# fin_solder.net
KiCad netlist of a schematic drawn in EAGLE
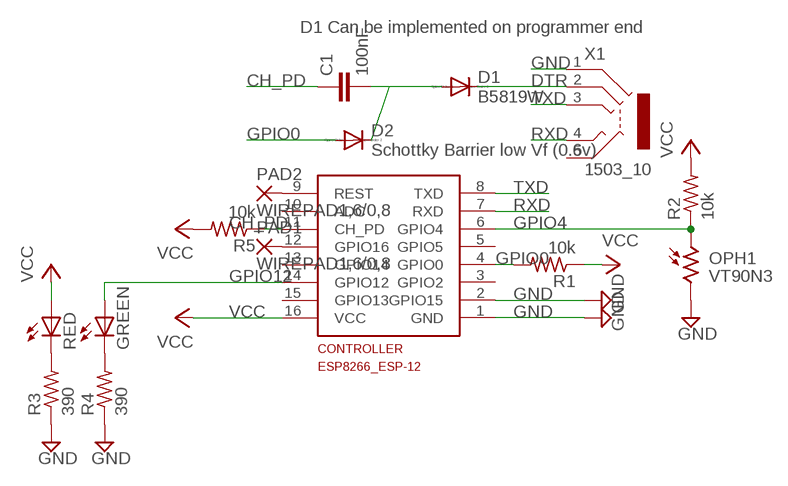
[diagram p0: schematic, sheet 1]

(export (version "E")
  (design (tool "Eeschema 10.0.6"))
  (components
    (comp (ref "C1")
      (value "100nF")
      (footprint "eagle-import:C0603")
      (libsource (lib "eagle-import") (part "C-EUC0603"))
    )
    (comp (ref "CONTROLLER")
      (value "ESP8266_ESP-12")
      (footprint "eagle-import:ESP8266-ESP12")
      (libsource (lib "eagle-import") (part "ESP8266_ESP-12"))
    )
    (comp (ref "D1")
      (value "B5819W")
      (footprint "eagle-import:D-7.5")
      (libsource (lib "eagle-import") (part "DIODE-D-7.5"))
    )
    (comp (ref "D2")
      (value "Schottky Barrier low Vf (0.6v)")
      (footprint "eagle-import:D-7.5")
      (libsource (lib "eagle-import") (part "DIODE-D-7.5"))
    )
    (comp (ref "GREEN")
      (value "LED3MM")
      (footprint "eagle-import:LED3MM")
      (libsource (lib "eagle-import") (part "LED3MM"))
    )
    (comp (ref "OPH1")
      (value "VT90N3")
      (footprint "eagle-import:VT900")
      (libsource (lib "eagle-import") (part "VT90N3"))
    )
    (comp (ref "PAD1")
      (value "WIREPAD1,6/0,8")
      (footprint "eagle-import:1,6_0,8")
      (libsource (lib "eagle-import") (part "WIREPAD1,6/0,8"))
    )
    (comp (ref "PAD2")
      (value "WIREPAD1,6/0,8")
      (footprint "eagle-import:1,6_0,8")
      (libsource (lib "eagle-import") (part "WIREPAD1,6/0,8"))
    )
    (comp (ref "R1")
      (value "10k")
      (footprint "eagle-import:0309_12")
      (libsource (lib "eagle-import") (part "R-US_0309/12"))
    )
    (comp (ref "R2")
      (value "10k")
      (footprint "eagle-import:0309_12")
      (libsource (lib "eagle-import") (part "R-US_0309/12"))
    )
    (comp (ref "R3")
      (value "390")
      (footprint "eagle-import:0309_12")
      (libsource (lib "eagle-import") (part "R-US_0309/12"))
    )
    (comp (ref "R4")
      (value "390")
      (footprint "eagle-import:0309_12")
      (libsource (lib "eagle-import") (part "R-US_0309/12"))
    )
    (comp (ref "R5")
      (value "10k")
      (footprint "eagle-import:0309_12")
      (libsource (lib "eagle-import") (part "R-US_0309/12"))
    )
    (comp (ref "RED")
      (value "LED3MM")
      (footprint "eagle-import:LED3MM")
      (libsource (lib "eagle-import") (part "LED3MM"))
    )
    (comp (ref "X1")
      (value "1503_10")
      (footprint "eagle-import:1503_10")
      (libsource (lib "eagle-import") (part "1503_10"))
    )
  )
  (nets
    (net (code "1") (name "/CH_PD") (class "Default")
      (node (ref "C1") (pin "1") (pinfunction "1_1") (pintype "passive"))
      (node (ref "CONTROLLER") (pin "11") (pinfunction "CH_PD_11") (pintype "bidirectional"))
      (node (ref "R5") (pin "1") (pinfunction "1_1") (pintype "passive"))
    )
    (net (code "2") (name "/DTR") (class "Default")
      (node (ref "D1") (pin "C") (pinfunction "C_C") (pintype "passive"))
      (node (ref "X1") (pin "2") (pinfunction "2_2") (pintype "passive"))
    )
    (net (code "3") (name "/GPIO0") (class "Default")
      (node (ref "CONTROLLER") (pin "4") (pinfunction "GPIO0_4") (pintype "bidirectional"))
      (node (ref "D2") (pin "A") (pinfunction "A_A") (pintype "passive"))
      (node (ref "R1") (pin "2") (pinfunction "2_2") (pintype "passive"))
    )
    (net (code "4") (name "/GPIO4") (class "Default")
      (node (ref "CONTROLLER") (pin "6") (pinfunction "GPIO4_6") (pintype "bidirectional"))
      (node (ref "OPH1") (pin "1") (pinfunction "1_1") (pintype "passive"))
      (node (ref "R2") (pin "1") (pinfunction "1_1") (pintype "passive"))
    )
    (net (code "5") (name "/GPIO12") (class "Default")
      (node (ref "CONTROLLER") (pin "14") (pinfunction "GPIO12_14") (pintype "bidirectional"))
      (node (ref "GREEN") (pin "A") (pinfunction "A_A") (pintype "passive"))
    )
    (net (code "6") (name "/RXD") (class "Default")
      (node (ref "CONTROLLER") (pin "7") (pinfunction "RXD_7") (pintype "bidirectional"))
      (node (ref "X1") (pin "4") (pinfunction "4_4") (pintype "passive"))
    )
    (net (code "7") (name "/TXD") (class "Default")
      (node (ref "CONTROLLER") (pin "8") (pinfunction "TXD_8") (pintype "bidirectional"))
      (node (ref "X1") (pin "3") (pinfunction "3_3") (pintype "passive"))
    )
    (net (code "8") (name "GND") (class "Default")
      (node (ref "CONTROLLER") (pin "1") (pinfunction "GND_1") (pintype "bidirectional"))
      (node (ref "CONTROLLER") (pin "2") (pinfunction "GPIO15_2") (pintype "bidirectional"))
      (node (ref "OPH1") (pin "2") (pinfunction "2_2") (pintype "passive"))
      (node (ref "R3") (pin "1") (pinfunction "1_1") (pintype "passive"))
      (node (ref "R4") (pin "1") (pinfunction "1_1") (pintype "passive"))
      (node (ref "X1") (pin "1") (pinfunction "1_1") (pintype "passive"))
    )
    (net (code "9") (name "Net-(C1-Pad2)") (class "Default")
      (node (ref "C1") (pin "2") (pinfunction "2_2") (pintype "passive"))
      (node (ref "D1") (pin "A") (pinfunction "A_A") (pintype "passive"))
      (node (ref "D2") (pin "C") (pinfunction "C_C") (pintype "passive"))
    )
    (net (code "10") (name "Net-(CONTROLLER-GPIO16)") (class "Default")
      (node (ref "CONTROLLER") (pin "12") (pinfunction "GPIO16_12") (pintype "bidirectional"))
      (node (ref "PAD1") (pin "1") (pinfunction "P_1") (pintype "passive"))
    )
    (net (code "11") (name "Net-(CONTROLLER-REST)") (class "Default")
      (node (ref "CONTROLLER") (pin "9") (pinfunction "REST_9") (pintype "bidirectional"))
      (node (ref "PAD2") (pin "1") (pinfunction "P_1") (pintype "passive"))
    )
    (net (code "12") (name "Net-(GREEN-C)") (class "Default")
      (node (ref "GREEN") (pin "K") (pinfunction "C_K") (pintype "passive"))
      (node (ref "R4") (pin "2") (pinfunction "2_2") (pintype "passive"))
    )
    (net (code "13") (name "Net-(RED-C)") (class "Default")
      (node (ref "R3") (pin "2") (pinfunction "2_2") (pintype "passive"))
      (node (ref "RED") (pin "K") (pinfunction "C_K") (pintype "passive"))
    )
    (net (code "14") (name "VCC") (class "Default")
      (node (ref "CONTROLLER") (pin "16") (pinfunction "VCC_16") (pintype "bidirectional"))
      (node (ref "R1") (pin "1") (pinfunction "1_1") (pintype "passive"))
      (node (ref "R2") (pin "2") (pinfunction "2_2") (pintype "passive"))
      (node (ref "R5") (pin "2") (pinfunction "2_2") (pintype "passive"))
      (node (ref "RED") (pin "A") (pinfunction "A_A") (pintype "passive"))
    )
    (net (code "15") (name "unconnected-(CONTROLLER-ADC-Pad10)") (class "Default")
      (node (ref "CONTROLLER") (pin "10") (pinfunction "ADC_10") (pintype "bidirectional"))
    )
    (net (code "16") (name "unconnected-(CONTROLLER-GPIO2-Pad3)") (class "Default")
      (node (ref "CONTROLLER") (pin "3") (pinfunction "GPIO2_3") (pintype "bidirectional"))
    )
    (net (code "17") (name "unconnected-(CONTROLLER-GPIO5-Pad5)") (class "Default")
      (node (ref "CONTROLLER") (pin "5") (pinfunction "GPIO5_5") (pintype "bidirectional"))
    )
    (net (code "18") (name "unconnected-(CONTROLLER-GPIO13-Pad15)") (class "Default")
      (node (ref "CONTROLLER") (pin "15") (pinfunction "GPIO13_15") (pintype "bidirectional"))
    )
    (net (code "19") (name "unconnected-(CONTROLLER-GPIO14-Pad13)") (class "Default")
      (node (ref "CONTROLLER") (pin "13") (pinfunction "GPIO14_13") (pintype "bidirectional"))
    )
    (net (code "20") (name "unconnected-(X1-Pad5)") (class "Default")
      (node (ref "X1") (pin "5") (pinfunction "5_5") (pintype "passive"))
    )
  )
)
